# IOB-Adapter-Input.net
KiCad netlist of a schematic drawn in EAGLE
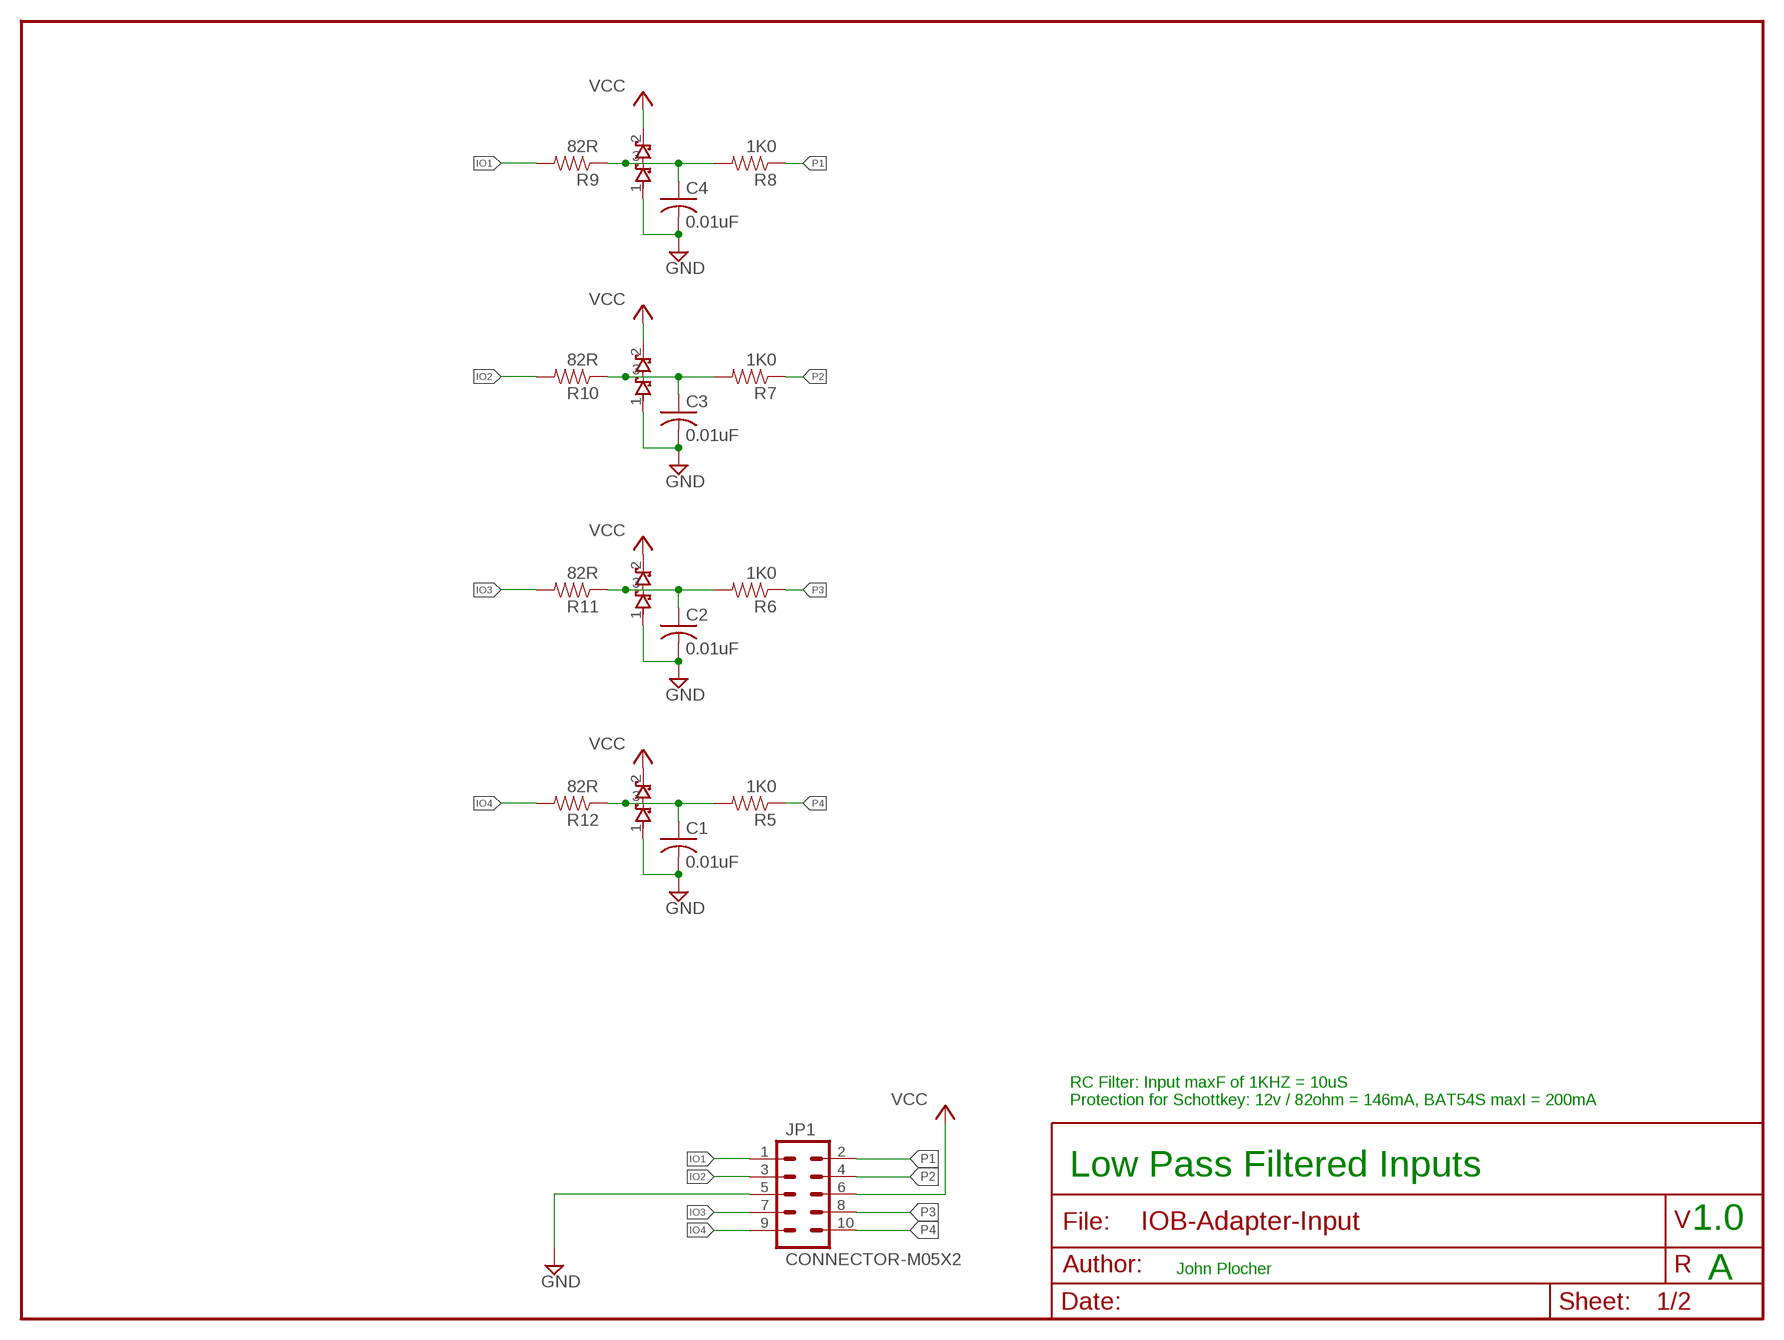
[diagram p0: schematic, sheet 1]
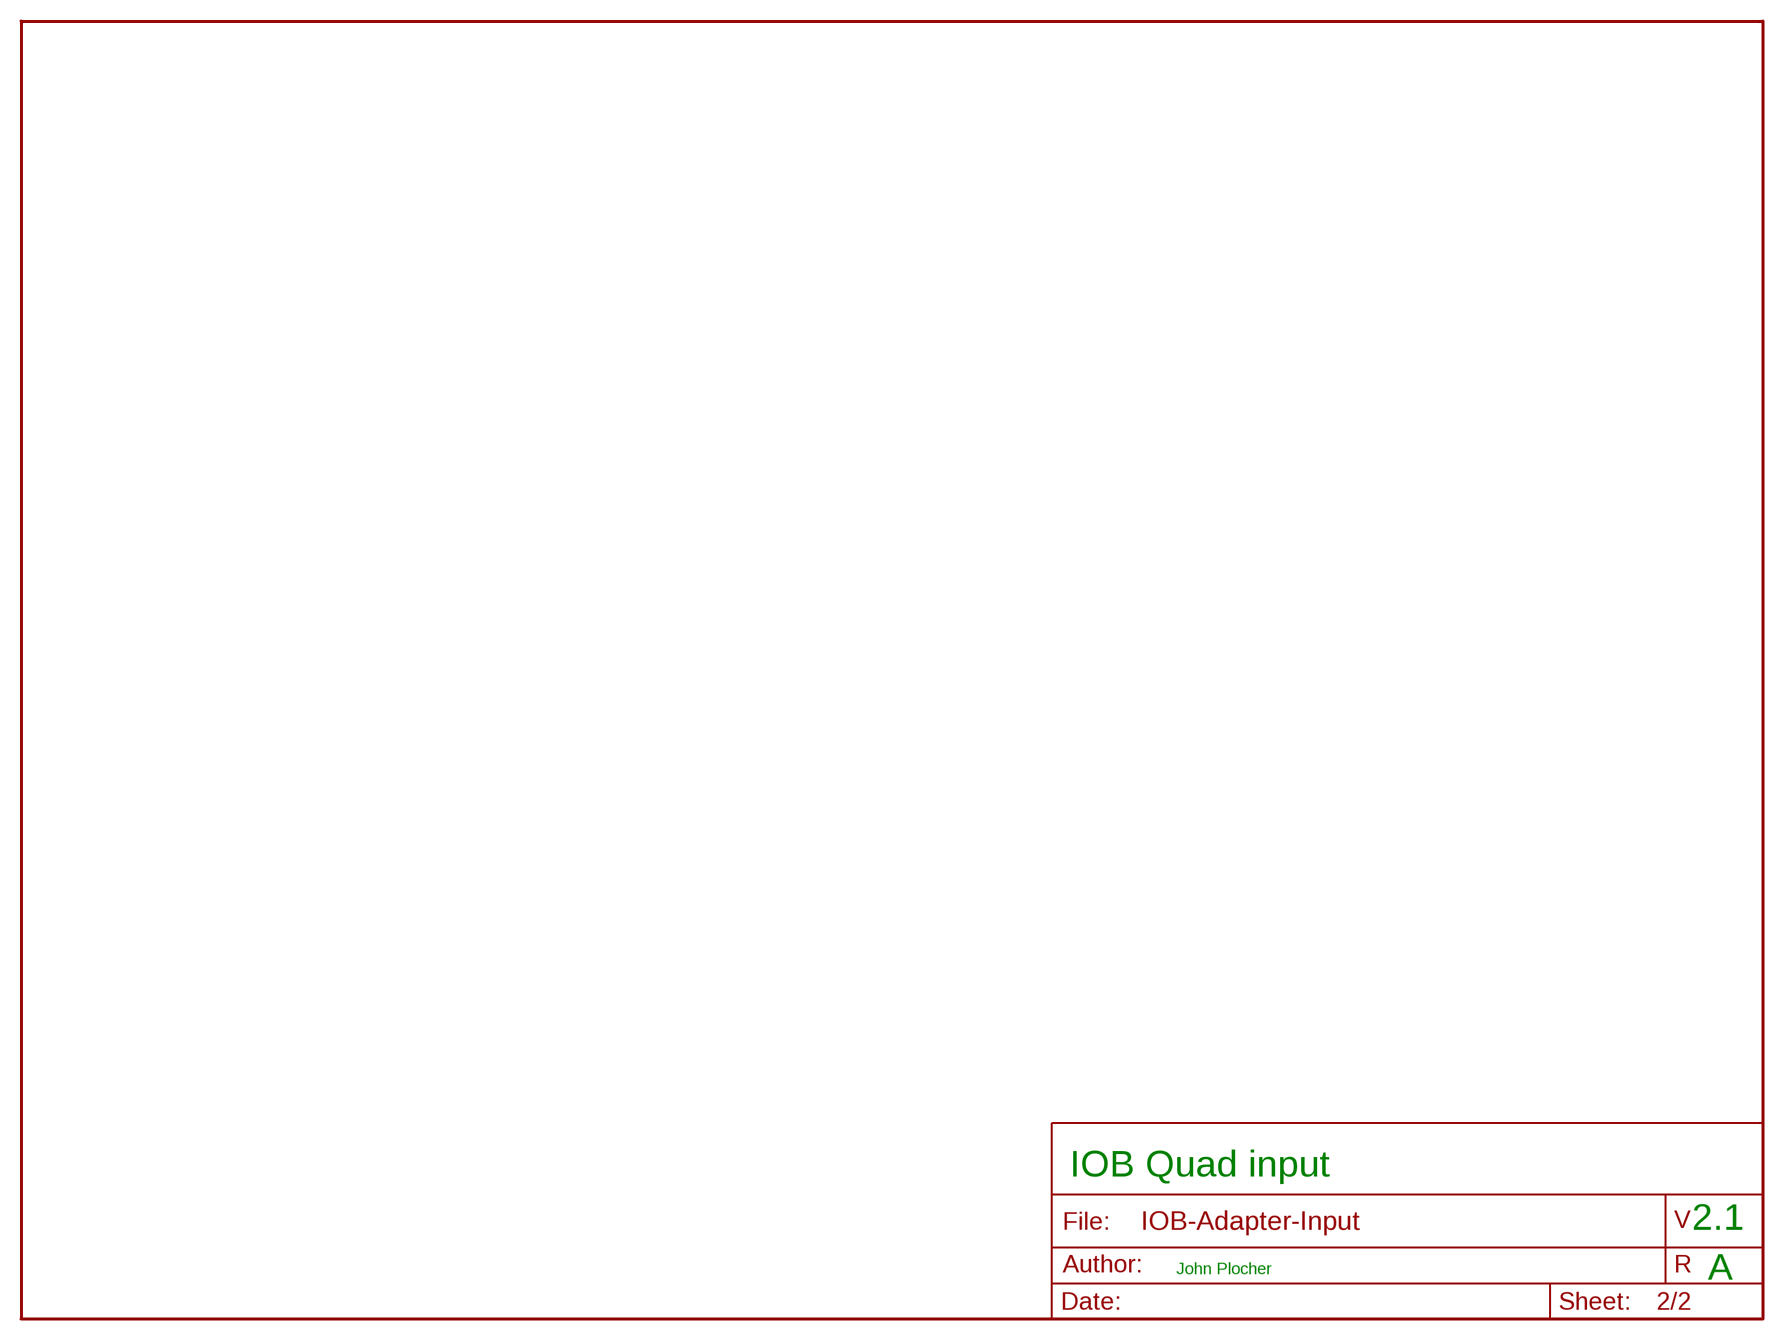
[diagram p1: schematic, sheet 2]

(export (version "E")
  (design (tool "Eeschema 10.0.6"))
  (components
    (comp (ref "C1")
      (value "0.01uF")
      (footprint "eagle-import:0603-CAP")
      (libsource (lib "eagle-import") (part "CAP0603"))
    )
    (comp (ref "C2")
      (value "0.01uF")
      (footprint "eagle-import:0603-CAP")
      (libsource (lib "eagle-import") (part "CAP0603"))
    )
    (comp (ref "C3")
      (value "0.01uF")
      (footprint "eagle-import:0603-CAP")
      (libsource (lib "eagle-import") (part "CAP0603"))
    )
    (comp (ref "C4")
      (value "0.01uF")
      (footprint "eagle-import:0603-CAP")
      (libsource (lib "eagle-import") (part "CAP0603"))
    )
    (comp (ref "D1")
      (value "BAT54S")
      (footprint "eagle-import:SOT23")
      (libsource (lib "eagle-import") (part "DIODE-BAT54S23"))
    )
    (comp (ref "D2")
      (value "BAT54S")
      (footprint "eagle-import:SOT23")
      (libsource (lib "eagle-import") (part "DIODE-BAT54S23"))
    )
    (comp (ref "D3")
      (value "BAT54S")
      (footprint "eagle-import:SOT23")
      (libsource (lib "eagle-import") (part "DIODE-BAT54S23"))
    )
    (comp (ref "D4")
      (value "BAT54S")
      (footprint "eagle-import:SOT23")
      (libsource (lib "eagle-import") (part "DIODE-BAT54S23"))
    )
    (comp (ref "JP1")
      (value "CONNECTOR-M05X2")
      (footprint "eagle-import:IOB-V3-MODULE")
      (libsource (lib "eagle-import") (part "CONNECTOR-M05X2"))
    )
    (comp (ref "R5")
      (value "1K0")
      (footprint "eagle-import:0603-RES")
      (libsource (lib "eagle-import") (part "R0603-RES"))
    )
    (comp (ref "R6")
      (value "1K0")
      (footprint "eagle-import:0603-RES")
      (libsource (lib "eagle-import") (part "R0603-RES"))
    )
    (comp (ref "R7")
      (value "1K0")
      (footprint "eagle-import:0603-RES")
      (libsource (lib "eagle-import") (part "R0603-RES"))
    )
    (comp (ref "R8")
      (value "1K0")
      (footprint "eagle-import:0603-RES")
      (libsource (lib "eagle-import") (part "R0603-RES"))
    )
    (comp (ref "R9")
      (value "82R")
      (footprint "eagle-import:0805-RES")
      (libsource (lib "eagle-import") (part "R0805-RES"))
    )
    (comp (ref "R10")
      (value "82R")
      (footprint "eagle-import:0805-RES")
      (libsource (lib "eagle-import") (part "R0805-RES"))
    )
    (comp (ref "R11")
      (value "82R")
      (footprint "eagle-import:0805-RES")
      (libsource (lib "eagle-import") (part "R0805-RES"))
    )
    (comp (ref "R12")
      (value "82R")
      (footprint "eagle-import:0805-RES")
      (libsource (lib "eagle-import") (part "R0805-RES"))
    )
  )
  (nets
    (net (code "1") (name "GND") (class "Default")
      (node (ref "C1") (pin "2") (pinfunction "2_2") (pintype "passive"))
      (node (ref "C2") (pin "2") (pinfunction "2_2") (pintype "passive"))
      (node (ref "C3") (pin "2") (pinfunction "2_2") (pintype "passive"))
      (node (ref "C4") (pin "2") (pinfunction "2_2") (pintype "passive"))
      (node (ref "D1") (pin "1") (pinfunction "A1_1") (pintype "bidirectional"))
      (node (ref "D2") (pin "1") (pinfunction "A1_1") (pintype "bidirectional"))
      (node (ref "D3") (pin "1") (pinfunction "A1_1") (pintype "bidirectional"))
      (node (ref "D4") (pin "1") (pinfunction "A1_1") (pintype "bidirectional"))
      (node (ref "JP1") (pin "5") (pinfunction "5_5") (pintype "passive"))
    )
    (net (code "2") (name "IO1") (class "Default")
      (node (ref "JP1") (pin "1") (pinfunction "1_1") (pintype "passive"))
      (node (ref "R9") (pin "2") (pinfunction "2_2") (pintype "passive"))
    )
    (net (code "3") (name "IO2") (class "Default")
      (node (ref "JP1") (pin "3") (pinfunction "3_3") (pintype "passive"))
      (node (ref "R10") (pin "2") (pinfunction "2_2") (pintype "passive"))
    )
    (net (code "4") (name "IO3") (class "Default")
      (node (ref "JP1") (pin "7") (pinfunction "7_7") (pintype "passive"))
      (node (ref "R11") (pin "2") (pinfunction "2_2") (pintype "passive"))
    )
    (net (code "5") (name "IO4") (class "Default")
      (node (ref "JP1") (pin "9") (pinfunction "9_9") (pintype "passive"))
      (node (ref "R12") (pin "2") (pinfunction "2_2") (pintype "passive"))
    )
    (net (code "6") (name "Net-(D1-COM)") (class "Default")
      (node (ref "C1") (pin "1") (pinfunction "1_1") (pintype "passive"))
      (node (ref "D1") (pin "3") (pinfunction "COM_3") (pintype "bidirectional"))
      (node (ref "R12") (pin "1") (pinfunction "1_1") (pintype "passive"))
      (node (ref "R5") (pin "2") (pinfunction "2_2") (pintype "passive"))
    )
    (net (code "7") (name "Net-(D2-COM)") (class "Default")
      (node (ref "C2") (pin "1") (pinfunction "1_1") (pintype "passive"))
      (node (ref "D2") (pin "3") (pinfunction "COM_3") (pintype "bidirectional"))
      (node (ref "R11") (pin "1") (pinfunction "1_1") (pintype "passive"))
      (node (ref "R6") (pin "2") (pinfunction "2_2") (pintype "passive"))
    )
    (net (code "8") (name "Net-(D3-COM)") (class "Default")
      (node (ref "C3") (pin "1") (pinfunction "1_1") (pintype "passive"))
      (node (ref "D3") (pin "3") (pinfunction "COM_3") (pintype "bidirectional"))
      (node (ref "R10") (pin "1") (pinfunction "1_1") (pintype "passive"))
      (node (ref "R7") (pin "2") (pinfunction "2_2") (pintype "passive"))
    )
    (net (code "9") (name "Net-(D4-COM)") (class "Default")
      (node (ref "C4") (pin "1") (pinfunction "1_1") (pintype "passive"))
      (node (ref "D4") (pin "3") (pinfunction "COM_3") (pintype "bidirectional"))
      (node (ref "R8") (pin "2") (pinfunction "2_2") (pintype "passive"))
      (node (ref "R9") (pin "1") (pinfunction "1_1") (pintype "passive"))
    )
    (net (code "10") (name "P1") (class "Default")
      (node (ref "JP1") (pin "2") (pinfunction "2_2") (pintype "passive"))
      (node (ref "R8") (pin "1") (pinfunction "1_1") (pintype "passive"))
    )
    (net (code "11") (name "P2") (class "Default")
      (node (ref "JP1") (pin "4") (pinfunction "4_4") (pintype "passive"))
      (node (ref "R7") (pin "1") (pinfunction "1_1") (pintype "passive"))
    )
    (net (code "12") (name "P3") (class "Default")
      (node (ref "JP1") (pin "8") (pinfunction "8_8") (pintype "passive"))
      (node (ref "R6") (pin "1") (pinfunction "1_1") (pintype "passive"))
    )
    (net (code "13") (name "P4") (class "Default")
      (node (ref "JP1") (pin "10") (pinfunction "10_10") (pintype "passive"))
      (node (ref "R5") (pin "1") (pinfunction "1_1") (pintype "passive"))
    )
    (net (code "14") (name "VCC") (class "Default")
      (node (ref "D1") (pin "2") (pinfunction "C2_2") (pintype "bidirectional"))
      (node (ref "D2") (pin "2") (pinfunction "C2_2") (pintype "bidirectional"))
      (node (ref "D3") (pin "2") (pinfunction "C2_2") (pintype "bidirectional"))
      (node (ref "D4") (pin "2") (pinfunction "C2_2") (pintype "bidirectional"))
      (node (ref "JP1") (pin "6") (pinfunction "6_6") (pintype "passive"))
    )
  )
)
